# Mega.net
KiCad netlist of a schematic drawn in EAGLE
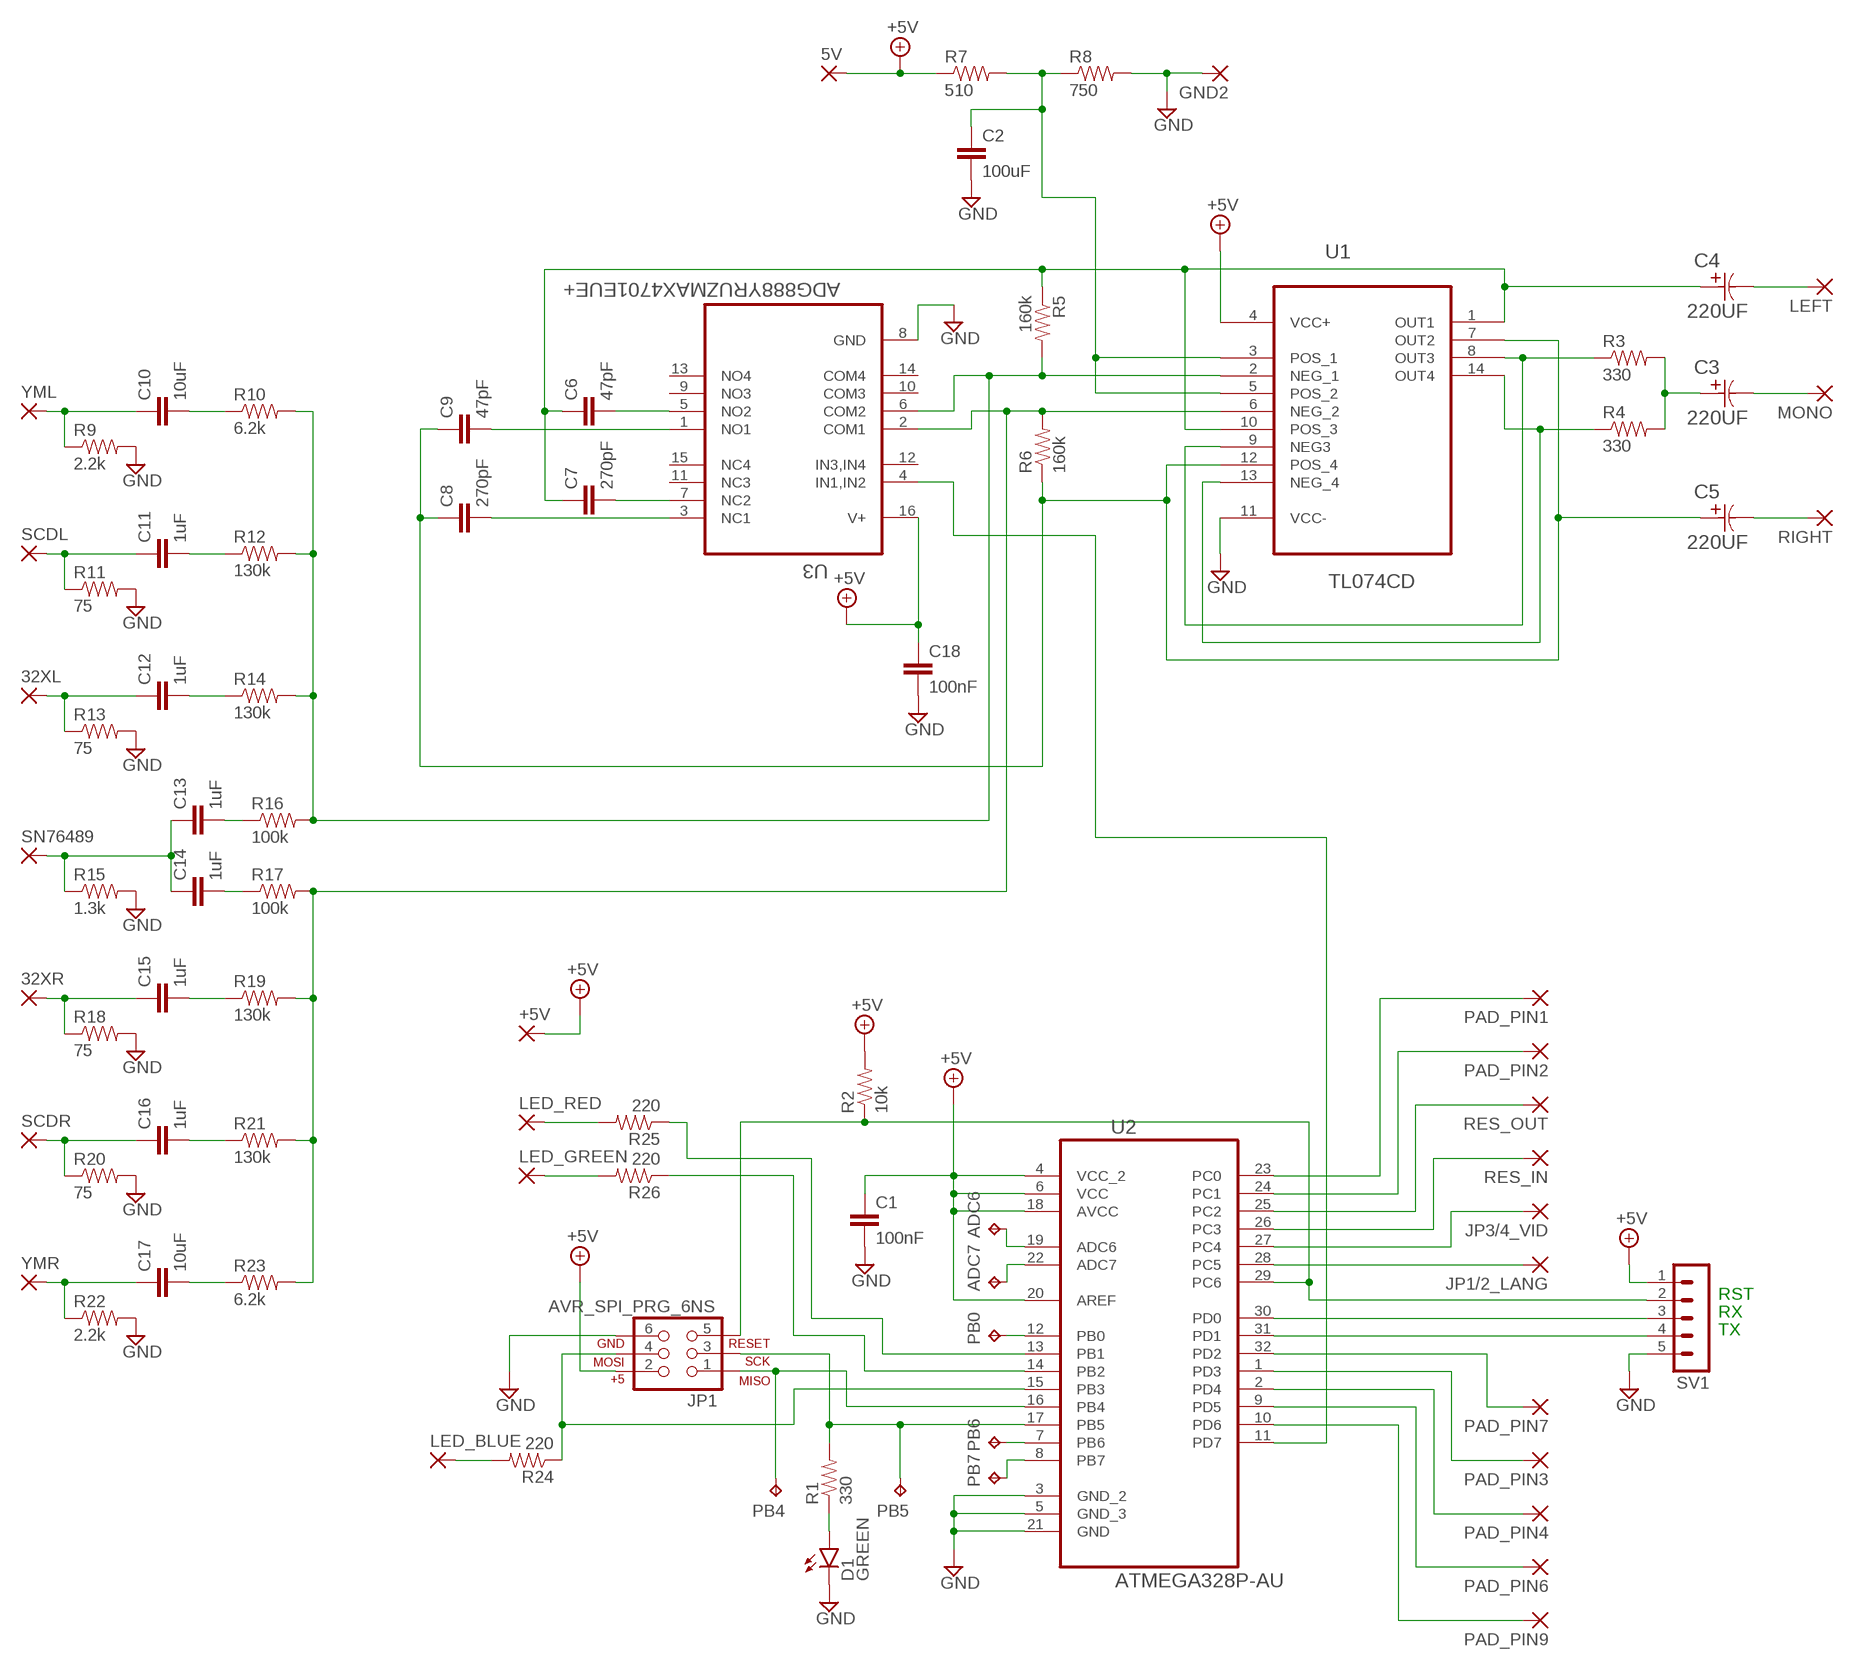
[diagram p0: schematic, sheet 1]

(export (version "E")
  (design (tool "Eeschema 10.0.6"))
  (components
    (comp (ref "+5V")
      (value "SMD2")
      (footprint "eagle-import:SMD1,27-2,54")
      (libsource (lib "eagle-import") (part "SMD2"))
    )
    (comp (ref "5V")
      (value "SMD2")
      (footprint "eagle-import:SMD1,27-2,54")
      (libsource (lib "eagle-import") (part "SMD2"))
    )
    (comp (ref "32XL")
      (value "SMD2")
      (footprint "eagle-import:SMD1,27-2,54")
      (libsource (lib "eagle-import") (part "SMD2"))
    )
    (comp (ref "32XR")
      (value "SMD2")
      (footprint "eagle-import:SMD1,27-2,54")
      (libsource (lib "eagle-import") (part "SMD2"))
    )
    (comp (ref "ADC6")
      (value "TPB1,27")
      (footprint "eagle-import:B1,27")
      (libsource (lib "eagle-import") (part "TPB1,27"))
    )
    (comp (ref "ADC7")
      (value "TPB1,27")
      (footprint "eagle-import:B1,27")
      (libsource (lib "eagle-import") (part "TPB1,27"))
    )
    (comp (ref "C1")
      (value "100nF")
      (footprint "eagle-import:1206")
      (libsource (lib "eagle-import") (part "CAP1206"))
    )
    (comp (ref "C2")
      (value "100uF")
      (footprint "eagle-import:1206")
      (libsource (lib "eagle-import") (part "CAP1206"))
    )
    (comp (ref "C3")
      (value "220UF")
      (footprint "eagle-import:CAPAE830X650N")
      (fields
        (field (name "MPN") "EEE-FK1C221P")
        (field (name "TOLERANCE") "±20 %")
        (field (name "TOLERANCE_1") "20 %")
      )
      (libsource (lib "eagle-import") (part "EEE--CASE-EFK1C221P"))
    )
    (comp (ref "C4")
      (value "220UF")
      (footprint "eagle-import:CAPAE830X650N")
      (fields
        (field (name "MPN") "EEE-FK1C221P")
        (field (name "TOLERANCE") "±20 %")
        (field (name "TOLERANCE_1") "20 %")
      )
      (libsource (lib "eagle-import") (part "EEE--CASE-EFK1C221P"))
    )
    (comp (ref "C5")
      (value "220UF")
      (footprint "eagle-import:CAPAE830X650N")
      (fields
        (field (name "MPN") "EEE-FK1C221P")
        (field (name "TOLERANCE") "±20 %")
        (field (name "TOLERANCE_1") "20 %")
      )
      (libsource (lib "eagle-import") (part "EEE--CASE-EFK1C221P"))
    )
    (comp (ref "C6")
      (value "47pF")
      (footprint "eagle-import:1206")
      (libsource (lib "eagle-import") (part "CAP1206"))
    )
    (comp (ref "C7")
      (value "270pF")
      (footprint "eagle-import:1206")
      (libsource (lib "eagle-import") (part "CAP1206"))
    )
    (comp (ref "C8")
      (value "270pF")
      (footprint "eagle-import:1206")
      (libsource (lib "eagle-import") (part "CAP1206"))
    )
    (comp (ref "C9")
      (value "47pF")
      (footprint "eagle-import:1206")
      (libsource (lib "eagle-import") (part "CAP1206"))
    )
    (comp (ref "C10")
      (value "10uF")
      (footprint "eagle-import:1206")
      (libsource (lib "eagle-import") (part "CAP1206"))
    )
    (comp (ref "C11")
      (value "1uF")
      (footprint "eagle-import:1206")
      (libsource (lib "eagle-import") (part "CAP1206"))
    )
    (comp (ref "C12")
      (value "1uF")
      (footprint "eagle-import:1206")
      (libsource (lib "eagle-import") (part "CAP1206"))
    )
    (comp (ref "C13")
      (value "1uF")
      (footprint "eagle-import:1206")
      (libsource (lib "eagle-import") (part "CAP1206"))
    )
    (comp (ref "C14")
      (value "1uF")
      (footprint "eagle-import:1206")
      (libsource (lib "eagle-import") (part "CAP1206"))
    )
    (comp (ref "C15")
      (value "1uF")
      (footprint "eagle-import:1206")
      (libsource (lib "eagle-import") (part "CAP1206"))
    )
    (comp (ref "C16")
      (value "1uF")
      (footprint "eagle-import:1206")
      (libsource (lib "eagle-import") (part "CAP1206"))
    )
    (comp (ref "C17")
      (value "10uF")
      (footprint "eagle-import:1206")
      (libsource (lib "eagle-import") (part "CAP1206"))
    )
    (comp (ref "C18")
      (value "100nF")
      (footprint "eagle-import:1206")
      (libsource (lib "eagle-import") (part "CAP1206"))
    )
    (comp (ref "D1")
      (value "GREEN")
      (footprint "eagle-import:LED-1206")
      (libsource (lib "eagle-import") (part "LED1206"))
    )
    (comp (ref "GND2")
      (value "SMD2")
      (footprint "eagle-import:SMD1,27-2,54")
      (libsource (lib "eagle-import") (part "SMD2"))
    )
    (comp (ref "JP1")
      (value "AVR_SPI_PRG_6NS")
      (footprint "eagle-import:2X3-NS")
      (libsource (lib "eagle-import") (part "AVR_SPI_PRG_6NS"))
    )
    (comp (ref "JP1/2_LANG")
      (value "SMD2")
      (footprint "eagle-import:SMD1,27-2,54")
      (libsource (lib "eagle-import") (part "SMD2"))
    )
    (comp (ref "JP3/4_VID")
      (value "SMD2")
      (footprint "eagle-import:SMD1,27-2,54")
      (libsource (lib "eagle-import") (part "SMD2"))
    )
    (comp (ref "LED_BLUE")
      (value "SMD2")
      (footprint "eagle-import:SMD1,27-2,54")
      (libsource (lib "eagle-import") (part "SMD2"))
    )
    (comp (ref "LED_GREEN")
      (value "SMD2")
      (footprint "eagle-import:SMD1,27-2,54")
      (libsource (lib "eagle-import") (part "SMD2"))
    )
    (comp (ref "LED_RED")
      (value "SMD2")
      (footprint "eagle-import:SMD1,27-2,54")
      (libsource (lib "eagle-import") (part "SMD2"))
    )
    (comp (ref "LEFT")
      (value "SMD2")
      (footprint "eagle-import:SMD1,27-2,54")
      (libsource (lib "eagle-import") (part "SMD2"))
    )
    (comp (ref "MONO")
      (value "SMD2")
      (footprint "eagle-import:SMD1,27-2,54")
      (libsource (lib "eagle-import") (part "SMD2"))
    )
    (comp (ref "PAD_PIN1")
      (value "SMD2")
      (footprint "eagle-import:SMD1,27-2,54")
      (libsource (lib "eagle-import") (part "SMD2"))
    )
    (comp (ref "PAD_PIN2")
      (value "SMD2")
      (footprint "eagle-import:SMD1,27-2,54")
      (libsource (lib "eagle-import") (part "SMD2"))
    )
    (comp (ref "PAD_PIN3")
      (value "SMD2")
      (footprint "eagle-import:SMD1,27-2,54")
      (libsource (lib "eagle-import") (part "SMD2"))
    )
    (comp (ref "PAD_PIN4")
      (value "SMD2")
      (footprint "eagle-import:SMD1,27-2,54")
      (libsource (lib "eagle-import") (part "SMD2"))
    )
    (comp (ref "PAD_PIN6")
      (value "SMD2")
      (footprint "eagle-import:SMD1,27-2,54")
      (libsource (lib "eagle-import") (part "SMD2"))
    )
    (comp (ref "PAD_PIN7")
      (value "SMD2")
      (footprint "eagle-import:SMD1,27-2,54")
      (libsource (lib "eagle-import") (part "SMD2"))
    )
    (comp (ref "PAD_PIN9")
      (value "SMD2")
      (footprint "eagle-import:SMD1,27-2,54")
      (libsource (lib "eagle-import") (part "SMD2"))
    )
    (comp (ref "PB0")
      (value "TPB1,27")
      (footprint "eagle-import:B1,27")
      (libsource (lib "eagle-import") (part "TPB1,27"))
    )
    (comp (ref "PB4")
      (value "TPB1,27")
      (footprint "eagle-import:B1,27")
      (libsource (lib "eagle-import") (part "TPB1,27"))
    )
    (comp (ref "PB5")
      (value "TPB1,27")
      (footprint "eagle-import:B1,27")
      (libsource (lib "eagle-import") (part "TPB1,27"))
    )
    (comp (ref "PB6")
      (value "TPB1,27")
      (footprint "eagle-import:B1,27")
      (libsource (lib "eagle-import") (part "TPB1,27"))
    )
    (comp (ref "PB7")
      (value "TPB1,27")
      (footprint "eagle-import:B1,27")
      (libsource (lib "eagle-import") (part "TPB1,27"))
    )
    (comp (ref "R1")
      (value "330")
      (footprint "eagle-import:1206")
      (libsource (lib "eagle-import") (part "RESISTOR1206"))
    )
    (comp (ref "R2")
      (value "10k")
      (footprint "eagle-import:1206")
      (libsource (lib "eagle-import") (part "RESISTOR1206"))
    )
    (comp (ref "R3")
      (value "330")
      (footprint "eagle-import:1206")
      (libsource (lib "eagle-import") (part "RESISTOR1206"))
    )
    (comp (ref "R4")
      (value "330")
      (footprint "eagle-import:1206")
      (libsource (lib "eagle-import") (part "RESISTOR1206"))
    )
    (comp (ref "R5")
      (value "160k")
      (footprint "eagle-import:1206")
      (libsource (lib "eagle-import") (part "RESISTOR1206"))
    )
    (comp (ref "R6")
      (value "160k")
      (footprint "eagle-import:1206")
      (libsource (lib "eagle-import") (part "RESISTOR1206"))
    )
    (comp (ref "R7")
      (value "510")
      (footprint "eagle-import:1206")
      (libsource (lib "eagle-import") (part "RESISTOR1206"))
    )
    (comp (ref "R8")
      (value "750")
      (footprint "eagle-import:1206")
      (libsource (lib "eagle-import") (part "RESISTOR1206"))
    )
    (comp (ref "R9")
      (value "2.2k")
      (footprint "eagle-import:1206")
      (libsource (lib "eagle-import") (part "RESISTOR1206"))
    )
    (comp (ref "R10")
      (value "6.2k")
      (footprint "eagle-import:1206")
      (libsource (lib "eagle-import") (part "RESISTOR1206"))
    )
    (comp (ref "R11")
      (value "75")
      (footprint "eagle-import:1206")
      (libsource (lib "eagle-import") (part "RESISTOR1206"))
    )
    (comp (ref "R12")
      (value "130k")
      (footprint "eagle-import:1206")
      (libsource (lib "eagle-import") (part "RESISTOR1206"))
    )
    (comp (ref "R13")
      (value "75")
      (footprint "eagle-import:1206")
      (libsource (lib "eagle-import") (part "RESISTOR1206"))
    )
    (comp (ref "R14")
      (value "130k")
      (footprint "eagle-import:1206")
      (libsource (lib "eagle-import") (part "RESISTOR1206"))
    )
    (comp (ref "R15")
      (value "1.3k")
      (footprint "eagle-import:1206")
      (libsource (lib "eagle-import") (part "RESISTOR1206"))
    )
    (comp (ref "R16")
      (value "100k")
      (footprint "eagle-import:1206")
      (libsource (lib "eagle-import") (part "RESISTOR1206"))
    )
    (comp (ref "R17")
      (value "100k")
      (footprint "eagle-import:1206")
      (libsource (lib "eagle-import") (part "RESISTOR1206"))
    )
    (comp (ref "R18")
      (value "75")
      (footprint "eagle-import:1206")
      (libsource (lib "eagle-import") (part "RESISTOR1206"))
    )
    (comp (ref "R19")
      (value "130k")
      (footprint "eagle-import:1206")
      (libsource (lib "eagle-import") (part "RESISTOR1206"))
    )
    (comp (ref "R20")
      (value "75")
      (footprint "eagle-import:1206")
      (libsource (lib "eagle-import") (part "RESISTOR1206"))
    )
    (comp (ref "R21")
      (value "130k")
      (footprint "eagle-import:1206")
      (libsource (lib "eagle-import") (part "RESISTOR1206"))
    )
    (comp (ref "R22")
      (value "2.2k")
      (footprint "eagle-import:1206")
      (libsource (lib "eagle-import") (part "RESISTOR1206"))
    )
    (comp (ref "R23")
      (value "6.2k")
      (footprint "eagle-import:1206")
      (libsource (lib "eagle-import") (part "RESISTOR1206"))
    )
    (comp (ref "R24")
      (value "220")
      (footprint "eagle-import:1206")
      (libsource (lib "eagle-import") (part "RESISTOR1206"))
    )
    (comp (ref "R25")
      (value "220")
      (footprint "eagle-import:1206")
      (libsource (lib "eagle-import") (part "RESISTOR1206"))
    )
    (comp (ref "R26")
      (value "220")
      (footprint "eagle-import:1206")
      (libsource (lib "eagle-import") (part "RESISTOR1206"))
    )
    (comp (ref "RES_IN")
      (value "SMD2")
      (footprint "eagle-import:SMD1,27-2,54")
      (libsource (lib "eagle-import") (part "SMD2"))
    )
    (comp (ref "RES_OUT")
      (value "SMD2")
      (footprint "eagle-import:SMD1,27-2,54")
      (libsource (lib "eagle-import") (part "SMD2"))
    )
    (comp (ref "RIGHT")
      (value "SMD2")
      (footprint "eagle-import:SMD1,27-2,54")
      (libsource (lib "eagle-import") (part "SMD2"))
    )
    (comp (ref "SCDL")
      (value "SMD2")
      (footprint "eagle-import:SMD1,27-2,54")
      (libsource (lib "eagle-import") (part "SMD2"))
    )
    (comp (ref "SCDR")
      (value "SMD2")
      (footprint "eagle-import:SMD1,27-2,54")
      (libsource (lib "eagle-import") (part "SMD2"))
    )
    (comp (ref "SN76489")
      (value "SMD2")
      (footprint "eagle-import:SMD1,27-2,54")
      (libsource (lib "eagle-import") (part "SMD2"))
    )
    (comp (ref "SV1")
      (value "MA05-1")
      (footprint "eagle-import:MA05-1")
      (libsource (lib "eagle-import") (part "MA05-1"))
    )
    (comp (ref "U1")
      (value "TL074CD")
      (footprint "eagle-import:SOIC127P600X175-14N")
      (libsource (lib "eagle-import") (part "TL074CD"))
    )
    (comp (ref "U2")
      (value "ATMEGA328P-AU")
      (footprint "eagle-import:QFP80P900X900X120-32N")
      (libsource (lib "eagle-import") (part "ATMEGA328P-AU"))
    )
    (comp (ref "U3")
      (value "ADG888YRUZMAX4701EUE+")
      (footprint "eagle-import:SOP65P640X120-16N")
      (libsource (lib "eagle-import") (part "ADG888YRUZMAX4701EUE+"))
    )
    (comp (ref "YML")
      (value "SMD2")
      (footprint "eagle-import:SMD1,27-2,54")
      (libsource (lib "eagle-import") (part "SMD2"))
    )
    (comp (ref "YMR")
      (value "SMD2")
      (footprint "eagle-import:SMD1,27-2,54")
      (libsource (lib "eagle-import") (part "SMD2"))
    )
  )
  (nets
    (net (code "1") (name "+5V") (class "Default")
      (node (ref "+5V") (pin "1") (pinfunction "P_1") (pintype "passive"))
      (node (ref "5V") (pin "1") (pinfunction "P_1") (pintype "passive"))
      (node (ref "C1") (pin "1") (pinfunction "1_1") (pintype "passive"))
      (node (ref "C18") (pin "1") (pinfunction "1_1") (pintype "passive"))
      (node (ref "JP1") (pin "2") (pinfunction "2_2") (pintype "passive"))
      (node (ref "R2") (pin "2") (pinfunction "2_2") (pintype "passive"))
      (node (ref "R7") (pin "1") (pinfunction "1_1") (pintype "passive"))
      (node (ref "SV1") (pin "1") (pinfunction "1_1") (pintype "passive"))
      (node (ref "U1") (pin "4") (pinfunction "VCC+_4") (pintype "power_in"))
      (node (ref "U2") (pin "18") (pinfunction "AVCC_18") (pintype "power_in"))
      (node (ref "U2") (pin "20") (pinfunction "AREF_20") (pintype "input"))
      (node (ref "U2") (pin "4") (pinfunction "VCC_2_4") (pintype "power_in"))
      (node (ref "U2") (pin "6") (pinfunction "VCC_6") (pintype "power_in"))
      (node (ref "U3") (pin "16") (pinfunction "V+_16") (pintype "power_in"))
    )
    (net (code "2") (name "GND") (class "Default")
      (node (ref "C1") (pin "2") (pinfunction "2_2") (pintype "passive"))
      (node (ref "C18") (pin "2") (pinfunction "2_2") (pintype "passive"))
      (node (ref "C2") (pin "2") (pinfunction "2_2") (pintype "passive"))
      (node (ref "D1") (pin "C") (pinfunction "C_C") (pintype "passive"))
      (node (ref "GND2") (pin "1") (pinfunction "P_1") (pintype "passive"))
      (node (ref "JP1") (pin "6") (pinfunction "6_6") (pintype "passive"))
      (node (ref "R11") (pin "2") (pinfunction "2_2") (pintype "passive"))
      (node (ref "R13") (pin "2") (pinfunction "2_2") (pintype "passive"))
      (node (ref "R15") (pin "2") (pinfunction "2_2") (pintype "passive"))
      (node (ref "R18") (pin "2") (pinfunction "2_2") (pintype "passive"))
      (node (ref "R20") (pin "2") (pinfunction "2_2") (pintype "passive"))
      (node (ref "R22") (pin "2") (pinfunction "2_2") (pintype "passive"))
      (node (ref "R8") (pin "2") (pinfunction "2_2") (pintype "passive"))
      (node (ref "R9") (pin "2") (pinfunction "2_2") (pintype "passive"))
      (node (ref "SV1") (pin "5") (pinfunction "5_5") (pintype "passive"))
      (node (ref "U1") (pin "11") (pinfunction "VCC-_11") (pintype "power_in"))
      (node (ref "U2") (pin "21") (pinfunction "GND_21") (pintype "passive"))
      (node (ref "U2") (pin "3") (pinfunction "GND_2_3") (pintype "passive"))
      (node (ref "U2") (pin "5") (pinfunction "GND_3_5") (pintype "passive"))
      (node (ref "U3") (pin "8") (pinfunction "GND_8") (pintype "passive"))
    )
    (net (code "3") (name "Net-(32XL-P)") (class "Default")
      (node (ref "32XL") (pin "1") (pinfunction "P_1") (pintype "passive"))
      (node (ref "C12") (pin "1") (pinfunction "1_1") (pintype "passive"))
      (node (ref "R13") (pin "1") (pinfunction "1_1") (pintype "passive"))
    )
    (net (code "4") (name "Net-(32XR-P)") (class "Default")
      (node (ref "32XR") (pin "1") (pinfunction "P_1") (pintype "passive"))
      (node (ref "C15") (pin "1") (pinfunction "1_1") (pintype "passive"))
      (node (ref "R18") (pin "1") (pinfunction "1_1") (pintype "passive"))
    )
    (net (code "5") (name "Net-(C3-Pad1)") (class "Default")
      (node (ref "C3") (pin "1") (pinfunction "1_1") (pintype "passive"))
      (node (ref "R3") (pin "2") (pinfunction "2_2") (pintype "passive"))
      (node (ref "R4") (pin "2") (pinfunction "2_2") (pintype "passive"))
    )
    (net (code "6") (name "Net-(C10-Pad2)") (class "Default")
      (node (ref "C10") (pin "2") (pinfunction "2_2") (pintype "passive"))
      (node (ref "R10") (pin "1") (pinfunction "1_1") (pintype "passive"))
    )
    (net (code "7") (name "Net-(C11-Pad2)") (class "Default")
      (node (ref "C11") (pin "2") (pinfunction "2_2") (pintype "passive"))
      (node (ref "R12") (pin "1") (pinfunction "1_1") (pintype "passive"))
    )
    (net (code "8") (name "Net-(C12-Pad2)") (class "Default")
      (node (ref "C12") (pin "2") (pinfunction "2_2") (pintype "passive"))
      (node (ref "R14") (pin "1") (pinfunction "1_1") (pintype "passive"))
    )
    (net (code "9") (name "Net-(C13-Pad2)") (class "Default")
      (node (ref "C13") (pin "2") (pinfunction "2_2") (pintype "passive"))
      (node (ref "R16") (pin "1") (pinfunction "1_1") (pintype "passive"))
    )
    (net (code "10") (name "Net-(C14-Pad2)") (class "Default")
      (node (ref "C14") (pin "2") (pinfunction "2_2") (pintype "passive"))
      (node (ref "R17") (pin "1") (pinfunction "1_1") (pintype "passive"))
    )
    (net (code "11") (name "Net-(C15-Pad2)") (class "Default")
      (node (ref "C15") (pin "2") (pinfunction "2_2") (pintype "passive"))
      (node (ref "R19") (pin "1") (pinfunction "1_1") (pintype "passive"))
    )
    (net (code "12") (name "Net-(C16-Pad2)") (class "Default")
      (node (ref "C16") (pin "2") (pinfunction "2_2") (pintype "passive"))
      (node (ref "R21") (pin "1") (pinfunction "1_1") (pintype "passive"))
    )
    (net (code "13") (name "Net-(C17-Pad2)") (class "Default")
      (node (ref "C17") (pin "2") (pinfunction "2_2") (pintype "passive"))
      (node (ref "R23") (pin "1") (pinfunction "1_1") (pintype "passive"))
    )
    (net (code "14") (name "Net-(D1-PadA)") (class "Default")
      (node (ref "D1") (pin "A") (pinfunction "A_A") (pintype "passive"))
      (node (ref "R1") (pin "1") (pinfunction "1_1") (pintype "passive"))
    )
    (net (code "15") (name "Net-(JP1/2_LANG-P)") (class "Default")
      (node (ref "JP1/2_LANG") (pin "1") (pinfunction "P_1") (pintype "passive"))
      (node (ref "U2") (pin "28") (pinfunction "PC5_28") (pintype "bidirectional"))
    )
    (net (code "16") (name "Net-(JP3/4_VID-P)") (class "Default")
      (node (ref "JP3/4_VID") (pin "1") (pinfunction "P_1") (pintype "passive"))
      (node (ref "U2") (pin "27") (pinfunction "PC4_27") (pintype "bidirectional"))
    )
    (net (code "17") (name "Net-(LED_BLUE-P)") (class "Default")
      (node (ref "LED_BLUE") (pin "1") (pinfunction "P_1") (pintype "passive"))
      (node (ref "R24") (pin "2") (pinfunction "2_2") (pintype "passive"))
    )
    (net (code "18") (name "Net-(LED_GREEN-P)") (class "Default")
      (node (ref "LED_GREEN") (pin "1") (pinfunction "P_1") (pintype "passive"))
      (node (ref "R26") (pin "2") (pinfunction "2_2") (pintype "passive"))
    )
    (net (code "19") (name "Net-(LED_RED-P)") (class "Default")
      (node (ref "LED_RED") (pin "1") (pinfunction "P_1") (pintype "passive"))
      (node (ref "R25") (pin "2") (pinfunction "2_2") (pintype "passive"))
    )
    (net (code "20") (name "Net-(LEFT-P)") (class "Default")
      (node (ref "C4") (pin "2") (pinfunction "2_2") (pintype "passive"))
      (node (ref "LEFT") (pin "1") (pinfunction "P_1") (pintype "passive"))
    )
    (net (code "21") (name "Net-(MONO-P)") (class "Default")
      (node (ref "C3") (pin "2") (pinfunction "2_2") (pintype "passive"))
      (node (ref "MONO") (pin "1") (pinfunction "P_1") (pintype "passive"))
    )
    (net (code "22") (name "Net-(PAD_PIN1-P)") (class "Default")
      (node (ref "PAD_PIN1") (pin "1") (pinfunction "P_1") (pintype "passive"))
      (node (ref "U2") (pin "23") (pinfunction "PC0_23") (pintype "bidirectional"))
    )
    (net (code "23") (name "Net-(PAD_PIN2-P)") (class "Default")
      (node (ref "PAD_PIN2") (pin "1") (pinfunction "P_1") (pintype "passive"))
      (node (ref "U2") (pin "24") (pinfunction "PC1_24") (pintype "bidirectional"))
    )
    (net (code "24") (name "Net-(PAD_PIN3-P)") (class "Default")
      (node (ref "PAD_PIN3") (pin "1") (pinfunction "P_1") (pintype "passive"))
      (node (ref "U2") (pin "1") (pinfunction "PD3_1") (pintype "bidirectional"))
    )
    (net (code "25") (name "Net-(PAD_PIN4-P)") (class "Default")
      (node (ref "PAD_PIN4") (pin "1") (pinfunction "P_1") (pintype "passive"))
      (node (ref "U2") (pin "2") (pinfunction "PD4_2") (pintype "bidirectional"))
    )
    (net (code "26") (name "Net-(PAD_PIN6-P)") (class "Default")
      (node (ref "PAD_PIN6") (pin "1") (pinfunction "P_1") (pintype "passive"))
      (node (ref "U2") (pin "9") (pinfunction "PD5_9") (pintype "bidirectional"))
    )
    (net (code "27") (name "Net-(PAD_PIN7-P)") (class "Default")
      (node (ref "PAD_PIN7") (pin "1") (pinfunction "P_1") (pintype "passive"))
      (node (ref "U2") (pin "32") (pinfunction "PD2_32") (pintype "bidirectional"))
    )
    (net (code "28") (name "Net-(PAD_PIN9-P)") (class "Default")
      (node (ref "PAD_PIN9") (pin "1") (pinfunction "P_1") (pintype "passive"))
      (node (ref "U2") (pin "10") (pinfunction "PD6_10") (pintype "bidirectional"))
    )
    (net (code "29") (name "Net-(RES_IN-P)") (class "Default")
      (node (ref "RES_IN") (pin "1") (pinfunction "P_1") (pintype "passive"))
      (node (ref "U2") (pin "26") (pinfunction "PC3_26") (pintype "bidirectional"))
    )
    (net (code "30") (name "Net-(RES_OUT-P)") (class "Default")
      (node (ref "RES_OUT") (pin "1") (pinfunction "P_1") (pintype "passive"))
      (node (ref "U2") (pin "25") (pinfunction "PC2_25") (pintype "bidirectional"))
    )
    (net (code "31") (name "Net-(RIGHT-P)") (class "Default")
      (node (ref "C5") (pin "2") (pinfunction "2_2") (pintype "passive"))
      (node (ref "RIGHT") (pin "1") (pinfunction "P_1") (pintype "passive"))
    )
    (net (code "32") (name "Net-(SCDL-P)") (class "Default")
      (node (ref "C11") (pin "1") (pinfunction "1_1") (pintype "passive"))
      (node (ref "R11") (pin "1") (pinfunction "1_1") (pintype "passive"))
      (node (ref "SCDL") (pin "1") (pinfunction "P_1") (pintype "passive"))
    )
    (net (code "33") (name "Net-(SCDR-P)") (class "Default")
      (node (ref "C16") (pin "1") (pinfunction "1_1") (pintype "passive"))
      (node (ref "R20") (pin "1") (pinfunction "1_1") (pintype "passive"))
      (node (ref "SCDR") (pin "1") (pinfunction "P_1") (pintype "passive"))
    )
    (net (code "34") (name "Net-(SN76489-P)") (class "Default")
      (node (ref "C13") (pin "1") (pinfunction "1_1") (pintype "passive"))
      (node (ref "C14") (pin "1") (pinfunction "1_1") (pintype "passive"))
      (node (ref "R15") (pin "1") (pinfunction "1_1") (pintype "passive"))
      (node (ref "SN76489") (pin "1") (pinfunction "P_1") (pintype "passive"))
    )
    (net (code "35") (name "Net-(U1-NEG3)") (class "Default")
      (node (ref "R3") (pin "1") (pinfunction "1_1") (pintype "passive"))
      (node (ref "U1") (pin "8") (pinfunction "OUT3_8") (pintype "output"))
      (node (ref "U1") (pin "9") (pinfunction "NEG3_9") (pintype "input"))
    )
    (net (code "36") (name "Net-(U1-NEG_1)") (class "Default")
      (node (ref "R10") (pin "2") (pinfunction "2_2") (pintype "passive"))
      (node (ref "R12") (pin "2") (pinfunction "2_2") (pintype "passive"))
      (node (ref "R14") (pin "2") (pinfunction "2_2") (pintype "passive"))
      (node (ref "R16") (pin "2") (pinfunction "2_2") (pintype "passive"))
      (node (ref "R5") (pin "2") (pinfunction "2_2") (pintype "passive"))
      (node (ref "U1") (pin "2") (pinfunction "NEG_1_2") (pintype "input"))
      (node (ref "U3") (pin "6") (pinfunction "COM2_6") (pintype "bidirectional"))
    )
    (net (code "37") (name "Net-(U1-NEG_2)") (class "Default")
      (node (ref "R17") (pin "2") (pinfunction "2_2") (pintype "passive"))
      (node (ref "R19") (pin "2") (pinfunction "2_2") (pintype "passive"))
      (node (ref "R21") (pin "2") (pinfunction "2_2") (pintype "passive"))
      (node (ref "R23") (pin "2") (pinfunction "2_2") (pintype "passive"))
      (node (ref "R6") (pin "2") (pinfunction "2_2") (pintype "passive"))
      (node (ref "U1") (pin "6") (pinfunction "NEG_2_6") (pintype "input"))
      (node (ref "U3") (pin "2") (pinfunction "COM1_2") (pintype "bidirectional"))
    )
    (net (code "38") (name "Net-(U1-NEG_4)") (class "Default")
      (node (ref "R4") (pin "1") (pinfunction "1_1") (pintype "passive"))
      (node (ref "U1") (pin "13") (pinfunction "NEG_4_13") (pintype "input"))
      (node (ref "U1") (pin "14") (pinfunction "OUT4_14") (pintype "output"))
    )
    (net (code "39") (name "Net-(U1-OUT1)") (class "Default")
      (node (ref "C4") (pin "1") (pinfunction "1_1") (pintype "passive"))
      (node (ref "C6") (pin "1") (pinfunction "1_1") (pintype "passive"))
      (node (ref "C7") (pin "1") (pinfunction "1_1") (pintype "passive"))
      (node (ref "R5") (pin "1") (pinfunction "1_1") (pintype "passive"))
      (node (ref "U1") (pin "1") (pinfunction "OUT1_1") (pintype "output"))
      (node (ref "U1") (pin "10") (pinfunction "POS_3_10") (pintype "input"))
    )
    (net (code "40") (name "Net-(U1-OUT2)") (class "Default")
      (node (ref "C5") (pin "1") (pinfunction "1_1") (pintype "passive"))
      (node (ref "C8") (pin "1") (pinfunction "1_1") (pintype "passive"))
      (node (ref "C9") (pin "1") (pinfunction "1_1") (pintype "passive"))
      (node (ref "R6") (pin "1") (pinfunction "1_1") (pintype "passive"))
      (node (ref "U1") (pin "12") (pinfunction "POS_4_12") (pintype "input"))
      (node (ref "U1") (pin "7") (pinfunction "OUT2_7") (pintype "output"))
    )
    (net (code "41") (name "Net-(U1-POS_1)") (class "Default")
      (node (ref "C2") (pin "1") (pinfunction "1_1") (pintype "passive"))
      (node (ref "R7") (pin "2") (pinfunction "2_2") (pintype "passive"))
      (node (ref "R8") (pin "1") (pinfunction "1_1") (pintype "passive"))
      (node (ref "U1") (pin "3") (pinfunction "POS_1_3") (pintype "input"))
      (node (ref "U1") (pin "5") (pinfunction "POS_2_5") (pintype "input"))
    )
    (net (code "42") (name "Net-(U2-ADC6)") (class "Default")
      (node (ref "ADC6") (pin "TP") (pinfunction "TP_TP") (pintype "input"))
      (node (ref "U2") (pin "19") (pinfunction "ADC6_19") (pintype "input"))
    )
    (net (code "43") (name "Net-(U2-ADC7)") (class "Default")
      (node (ref "ADC7") (pin "TP") (pinfunction "TP_TP") (pintype "input"))
      (node (ref "U2") (pin "22") (pinfunction "ADC7_22") (pintype "input"))
    )
    (net (code "44") (name "Net-(U2-PB0)") (class "Default")
      (node (ref "PB0") (pin "TP") (pinfunction "TP_TP") (pintype "input"))
      (node (ref "U2") (pin "12") (pinfunction "PB0_12") (pintype "bidirectional"))
    )
    (net (code "45") (name "Net-(U2-PB1)") (class "Default")
      (node (ref "R25") (pin "1") (pinfunction "1_1") (pintype "passive"))
      (node (ref "U2") (pin "13") (pinfunction "PB1_13") (pintype "bidirectional"))
    )
    (net (code "46") (name "Net-(U2-PB2)") (class "Default")
      (node (ref "R26") (pin "1") (pinfunction "1_1") (pintype "passive"))
      (node (ref "U2") (pin "14") (pinfunction "PB2_14") (pintype "bidirectional"))
    )
    (net (code "47") (name "Net-(U2-PB3)") (class "Default")
      (node (ref "JP1") (pin "4") (pinfunction "4_4") (pintype "passive"))
      (node (ref "R24") (pin "1") (pinfunction "1_1") (pintype "passive"))
      (node (ref "U2") (pin "15") (pinfunction "PB3_15") (pintype "bidirectional"))
    )
    (net (code "48") (name "Net-(U2-PB4)") (class "Default")
      (node (ref "JP1") (pin "1") (pinfunction "1_1") (pintype "passive"))
      (node (ref "PB4") (pin "TP") (pinfunction "TP_TP") (pintype "input"))
      (node (ref "U2") (pin "16") (pinfunction "PB4_16") (pintype "bidirectional"))
    )
    (net (code "49") (name "Net-(U2-PB5)") (class "Default")
      (node (ref "JP1") (pin "3") (pinfunction "3_3") (pintype "passive"))
      (node (ref "PB5") (pin "TP") (pinfunction "TP_TP") (pintype "input"))
      (node (ref "R1") (pin "2") (pinfunction "2_2") (pintype "passive"))
      (node (ref "U2") (pin "17") (pinfunction "PB5_17") (pintype "bidirectional"))
    )
    (net (code "50") (name "Net-(U2-PB6)") (class "Default")
      (node (ref "PB6") (pin "TP") (pinfunction "TP_TP") (pintype "input"))
      (node (ref "U2") (pin "7") (pinfunction "PB6_7") (pintype "bidirectional"))
    )
    (net (code "51") (name "Net-(U2-PB7)") (class "Default")
      (node (ref "PB7") (pin "TP") (pinfunction "TP_TP") (pintype "input"))
      (node (ref "U2") (pin "8") (pinfunction "PB7_8") (pintype "bidirectional"))
    )
    (net (code "52") (name "Net-(U2-PC6)") (class "Default")
      (node (ref "JP1") (pin "5") (pinfunction "5_5") (pintype "passive"))
      (node (ref "R2") (pin "1") (pinfunction "1_1") (pintype "passive"))
      (node (ref "SV1") (pin "2") (pinfunction "2_2") (pintype "passive"))
      (node (ref "U2") (pin "29") (pinfunction "PC6_29") (pintype "bidirectional"))
    )
    (net (code "53") (name "Net-(U2-PD0)") (class "Default")
      (node (ref "SV1") (pin "3") (pinfunction "3_3") (pintype "passive"))
      (node (ref "U2") (pin "30") (pinfunction "PD0_30") (pintype "bidirectional"))
    )
    (net (code "54") (name "Net-(U2-PD1)") (class "Default")
      (node (ref "SV1") (pin "4") (pinfunction "4_4") (pintype "passive"))
      (node (ref "U2") (pin "31") (pinfunction "PD1_31") (pintype "bidirectional"))
    )
    (net (code "55") (name "Net-(U2-PD7)") (class "Default")
      (node (ref "U2") (pin "11") (pinfunction "PD7_11") (pintype "bidirectional"))
      (node (ref "U3") (pin "4") (pinfunction "IN1,IN2_4") (pintype "input"))
    )
    (net (code "56") (name "Net-(U3-NC1)") (class "Default")
      (node (ref "C8") (pin "2") (pinfunction "2_2") (pintype "passive"))
      (node (ref "U3") (pin "3") (pinfunction "NC1_3") (pintype "bidirectional"))
    )
    (net (code "57") (name "Net-(U3-NC2)") (class "Default")
      (node (ref "C7") (pin "2") (pinfunction "2_2") (pintype "passive"))
      (node (ref "U3") (pin "7") (pinfunction "NC2_7") (pintype "bidirectional"))
    )
    (net (code "58") (name "Net-(U3-NO1)") (class "Default")
      (node (ref "C9") (pin "2") (pinfunction "2_2") (pintype "passive"))
      (node (ref "U3") (pin "1") (pinfunction "NO1_1") (pintype "bidirectional"))
    )
    (net (code "59") (name "Net-(U3-NO2)") (class "Default")
      (node (ref "C6") (pin "2") (pinfunction "2_2") (pintype "passive"))
      (node (ref "U3") (pin "5") (pinfunction "NO2_5") (pintype "bidirectional"))
    )
    (net (code "60") (name "Net-(YML-P)") (class "Default")
      (node (ref "C10") (pin "1") (pinfunction "1_1") (pintype "passive"))
      (node (ref "R9") (pin "1") (pinfunction "1_1") (pintype "passive"))
      (node (ref "YML") (pin "1") (pinfunction "P_1") (pintype "passive"))
    )
    (net (code "61") (name "Net-(YMR-P)") (class "Default")
      (node (ref "C17") (pin "1") (pinfunction "1_1") (pintype "passive"))
      (node (ref "R22") (pin "1") (pinfunction "1_1") (pintype "passive"))
      (node (ref "YMR") (pin "1") (pinfunction "P_1") (pintype "passive"))
    )
    (net (code "62") (name "unconnected-(U3-COM3-Pad10)") (class "Default")
      (node (ref "U3") (pin "10") (pinfunction "COM3_10") (pintype "bidirectional"))
    )
    (net (code "63") (name "unconnected-(U3-COM4-Pad14)") (class "Default")
      (node (ref "U3") (pin "14") (pinfunction "COM4_14") (pintype "bidirectional"))
    )
    (net (code "64") (name "unconnected-(U3-IN3,IN4-Pad12)") (class "Default")
      (node (ref "U3") (pin "12") (pinfunction "IN3,IN4_12") (pintype "input"))
    )
    (net (code "65") (name "unconnected-(U3-NC3-Pad11)") (class "Default")
      (node (ref "U3") (pin "11") (pinfunction "NC3_11") (pintype "bidirectional"))
    )
    (net (code "66") (name "unconnected-(U3-NC4-Pad15)") (class "Default")
      (node (ref "U3") (pin "15") (pinfunction "NC4_15") (pintype "bidirectional"))
    )
    (net (code "67") (name "unconnected-(U3-NO3-Pad9)") (class "Default")
      (node (ref "U3") (pin "9") (pinfunction "NO3_9") (pintype "bidirectional"))
    )
    (net (code "68") (name "unconnected-(U3-NO4-Pad13)") (class "Default")
      (node (ref "U3") (pin "13") (pinfunction "NO4_13") (pintype "bidirectional"))
    )
  )
)
